# pmu.net
KiCad netlist of a schematic drawn in Altium Designer
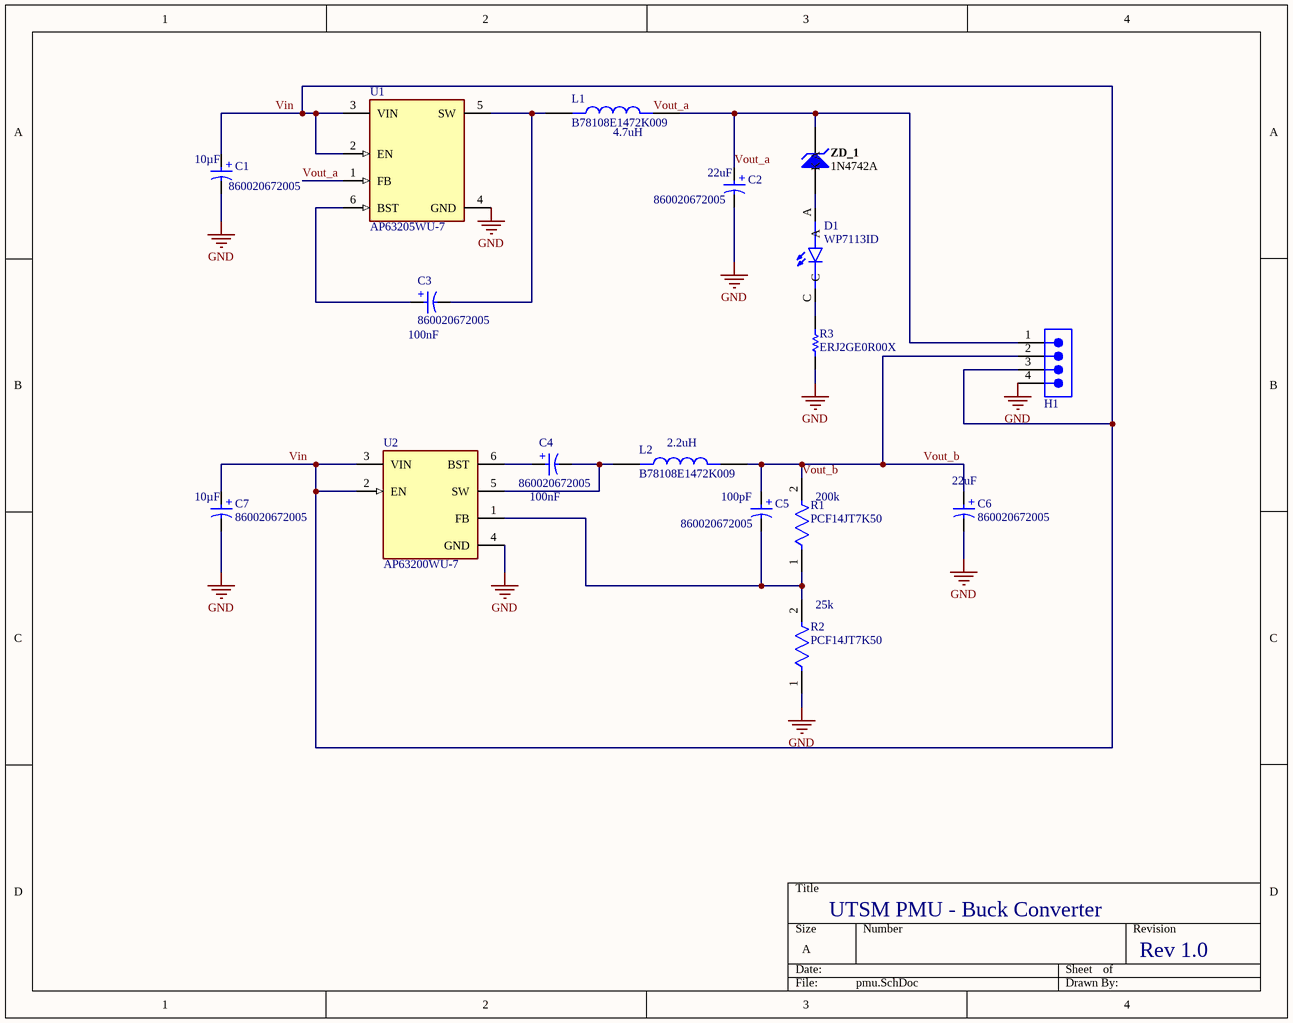
[diagram p0: pmu.SchDoc]

(export (version "E")
  (design (tool "Eeschema 10.0.6"))
  (components
    (comp (ref "C1")
      (value "860020672005")
      (footprint "WCAP-ATG5_D5H11")
      (description "860020672005 WCAP-ATG5 Aluminum Electrolytic Capacitors")
      (fields (field (name "TOLERANCE") "20%") (field (name "CAPACITANCE") "10µF"))
      (libsource (lib "Altium Content Vault") (part "Capacitor_Polarized"))
    )
    (comp (ref "C2")
      (value "860020672005")
      (footprint "WCAP-ATG5_D5H11")
      (description "860020672005 WCAP-ATG5 Aluminum Electrolytic Capacitors")
      (fields (field (name "TOLERANCE") "20%") (field (name "CAPACITANCE") "22uF"))
      (libsource (lib "Altium Content Vault") (part "Capacitor_Polarized"))
    )
    (comp (ref "C3")
      (value "860020672005")
      (footprint "WCAP-ATG5_D5H11")
      (description "860020672005 WCAP-ATG5 Aluminum Electrolytic Capacitors")
      (fields (field (name "TOLERANCE") "20%") (field (name "CAPACITANCE") "100nF"))
      (libsource (lib "Altium Content Vault") (part "Capacitor_Polarized"))
    )
    (comp (ref "C4")
      (value "860020672005")
      (footprint "WCAP-ATG5_D5H11")
      (description "860020672005 WCAP-ATG5 Aluminum Electrolytic Capacitors")
      (fields (field (name "TOLERANCE") "20%") (field (name "CAPACITANCE") "100nF"))
      (libsource (lib "Altium Content Vault") (part "Capacitor_Polarized"))
    )
    (comp (ref "C5")
      (value "860020672005")
      (footprint "WCAP-ATG5_D5H11")
      (description "860020672005 WCAP-ATG5 Aluminum Electrolytic Capacitors")
      (fields (field (name "TOLERANCE") "20%") (field (name "CAPACITANCE") "100pF"))
      (libsource (lib "Altium Content Vault") (part "Capacitor_Polarized"))
    )
    (comp (ref "C6")
      (value "860020672005")
      (footprint "WCAP-ATG5_D5H11")
      (description "860020672005 WCAP-ATG5 Aluminum Electrolytic Capacitors")
      (fields (field (name "TOLERANCE") "20%") (field (name "CAPACITANCE") "22uF"))
      (libsource (lib "Altium Content Vault") (part "Capacitor_Polarized"))
    )
    (comp (ref "C7")
      (value "860020672005")
      (footprint "WCAP-ATG5_D5H11")
      (description "860020672005 WCAP-ATG5 Aluminum Electrolytic Capacitors")
      (fields (field (name "TOLERANCE") "20%") (field (name "CAPACITANCE") "10µF"))
      (libsource (lib "Altium Content Vault") (part "Capacitor_Polarized"))
    )
    (comp (ref "D1")
      (value "WP7113ID")
      (footprint "LED_WP7113ID")
      (description "Red 617nm LED Indication - Discrete 2V Radial")
      (fields (field (name "MF") "Kingbright"))
      (libsource (lib "leds-WP7113ID") (part "WP7113ID"))
    )
    (comp (ref "H1")
      (value "61300411121")
      (footprint "61300411121")
      (description "WR-PHD Pin Header, THT, Vertical, pitch 2.54mm, 1 Row, 4P")
      (fields (field (name "MANUFACTURER") "Wurth Elektronik"))
      (libsource (lib "pmu") (part "61300411121"))
    )
    (comp (ref "L1")
      (value "B78108E1472K009")
      (footprint "INDAD1430W80L950D400")
      (description "4.7 ÂµH Unshielded Drum Core, Wirewound Inductor 2.75 A 85mOhm Max Axial")
      (fields
        (field (name "ALTIUM_VALUE") "4.7uH")
        (field (name "DIGI-KEY_PART_NUMBER") "495-76025-1-ND")
        (field (name "MF") "EPCOS")
      )
      (libsource (lib "B78108E1472K009") (part "B78108E1472K009"))
    )
    (comp (ref "L2")
      (value "B78108E1472K009")
      (footprint "INDAD1430W80L950D400")
      (description "4.7 ÂµH Unshielded Drum Core, Wirewound Inductor 2.75 A 85mOhm Max Axial")
      (fields
        (field (name "ALTIUM_VALUE") "2.2uH")
        (field (name "DIGI-KEY_PART_NUMBER") "495-76025-1-ND")
        (field (name "MF") "EPCOS")
      )
      (libsource (lib "B78108E1472K009") (part "B78108E1472K009"))
    )
    (comp (ref "R1")
      (value "PCF14JT7K50")
      (footprint "FP-CF14-MFG")
      (description "RES 7.5K OHM 1/4W 5% AXIAL")
      (fields (field (name "RESISTANCE") "200k") (field (name "TOLERANCE") "5%"))
      (libsource (lib "Altium Content Vault") (part "1029c3af85768c4190bb7ad29bc67b5"))
    )
    (comp (ref "R2")
      (value "PCF14JT7K50")
      (footprint "FP-CF14-MFG")
      (description "RES 7.5K OHM 1/4W 5% AXIAL")
      (fields (field (name "RESISTANCE") "25k") (field (name "TOLERANCE") "5%"))
      (libsource (lib "Altium Content Vault") (part "1029c3af85768c4190bb7ad29bc67b5"))
    )
    (comp (ref "R3")
      (value "ERJ2GE0R00X")
      (footprint "RESC1005X40X25LL05T05")
      (description "Chip Resistor, 0 Ohm, 0.1 W, -55 to 155 degC, 0402 (1005 Metric), RoHS, Tape and Reel")
      (fields (field (name "MANUFACTURER") "Panasonic") (field (name "TOLERANCE") "5%"))
      (libsource (lib "Altium Content Vault") (part "RES-2"))
    )
    (comp (ref "U1")
      (value "AP63205WU-7")
      (footprint "FP-TSOT26-MFG")
      (description "IC REG BUCK 5V 2A TSOT26")
      (fields
        (field (name "MANUFACTURER") "Diodes Inc.")
        (field (name "OCTOPART") "https://octopart.com/ap63205wu-7-diodes+inc.-98099551")
      )
      (libsource (lib "Altium Content Vault") (part "029bc9fbfa4a99dbb8b3a24c2adb655"))
    )
    (comp (ref "U2")
      (value "AP63200WU-7")
      (footprint "FP-TSOT26-MFG")
      (description "IC REG BUCK ADJUSTABLE 2A TSOT26")
      (fields
        (field (name "OCTOPART") "https://octopart.com/ap63200wu-7-diodes+inc.-98099548")
        (field (name "MANUFACTURER") "Diodes Inc.")
      )
      (libsource (lib "Altium Content Vault") (part "2ae3aed49e7ee94ca813948749813a1"))
    )
    (comp (ref "ZD_1")
      (value "1N4742A")
      (footprint "FAIR-DO-41-2_V")
      (description "Zener Diode, 12V, 1W, 5%, -65 to 200 degC, 2-Pin DO-41, Body 2.72 x 5.2 mm, RoHS")
      (fields (field (name "TOLERANCE") "5%") (field (name "MANUFACTURER") "Fairchild Semiconductor"))
      (libsource (lib "Altium Content Vault") (part "FAIR-DZEN-A1K2-2"))
    )
  )
  (nets
    (net (code "1") (name "/Vin") (class "Default")
      (node (ref "C1") (pin "1") (pinfunction "P_1") (pintype "passive"))
      (node (ref "C7") (pin "1") (pinfunction "P_1") (pintype "passive"))
      (node (ref "H1") (pin "3") (pinfunction "3_3") (pintype "passive"))
      (node (ref "U1") (pin "2") (pinfunction "EN_2") (pintype "input"))
      (node (ref "U1") (pin "3") (pinfunction "VIN_3") (pintype "power_in"))
      (node (ref "U2") (pin "2") (pinfunction "EN_2") (pintype "input"))
      (node (ref "U2") (pin "3") (pinfunction "VIN_3") (pintype "power_in"))
    )
    (net (code "2") (name "/Vout_a") (class "Default")
      (node (ref "C2") (pin "1") (pinfunction "P_1") (pintype "passive"))
      (node (ref "H1") (pin "1") (pinfunction "1_1") (pintype "passive"))
      (node (ref "L1") (pin "2") (pinfunction "2_2") (pintype "passive"))
      (node (ref "U1") (pin "1") (pinfunction "FB_1") (pintype "input"))
      (node (ref "ZD_1") (pin "2") (pinfunction "K_2") (pintype "passive"))
    )
    (net (code "3") (name "/Vout_b") (class "Default")
      (node (ref "C5") (pin "1") (pinfunction "P_1") (pintype "passive"))
      (node (ref "C6") (pin "1") (pinfunction "P_1") (pintype "passive"))
      (node (ref "H1") (pin "2") (pinfunction "2_2") (pintype "passive"))
      (node (ref "L2") (pin "2") (pinfunction "2_2") (pintype "passive"))
      (node (ref "R1") (pin "2") (pinfunction "2_2") (pintype "passive"))
    )
    (net (code "4") (name "GND") (class "Default")
      (node (ref "C1") (pin "2") (pinfunction "N_2") (pintype "passive"))
      (node (ref "C2") (pin "2") (pinfunction "N_2") (pintype "passive"))
      (node (ref "C6") (pin "2") (pinfunction "N_2") (pintype "passive"))
      (node (ref "C7") (pin "2") (pinfunction "N_2") (pintype "passive"))
      (node (ref "H1") (pin "4") (pinfunction "4_4") (pintype "passive"))
      (node (ref "R2") (pin "1") (pinfunction "1_1") (pintype "passive"))
      (node (ref "R3") (pin "1") (pinfunction "1_1") (pintype "passive"))
      (node (ref "U1") (pin "4") (pinfunction "GND_4") (pintype "power_in"))
      (node (ref "U2") (pin "4") (pinfunction "GND_4") (pintype "power_in"))
    )
    (net (code "5") (name "Net-(C3-N)") (class "Default")
      (node (ref "C3") (pin "2") (pinfunction "N_2") (pintype "passive"))
      (node (ref "L1") (pin "1") (pinfunction "1_1") (pintype "passive"))
      (node (ref "U1") (pin "5") (pinfunction "SW_5") (pintype "power_in"))
    )
    (net (code "6") (name "Net-(C3-P)") (class "Default")
      (node (ref "C3") (pin "1") (pinfunction "P_1") (pintype "passive"))
      (node (ref "U1") (pin "6") (pinfunction "BST_6") (pintype "input"))
    )
    (net (code "7") (name "Net-(C4-N)") (class "Default")
      (node (ref "C4") (pin "2") (pinfunction "N_2") (pintype "passive"))
      (node (ref "L2") (pin "1") (pinfunction "1_1") (pintype "passive"))
      (node (ref "U2") (pin "5") (pinfunction "SW_5") (pintype "passive"))
    )
    (net (code "8") (name "Net-(C4-P)") (class "Default")
      (node (ref "C4") (pin "1") (pinfunction "P_1") (pintype "passive"))
      (node (ref "U2") (pin "6") (pinfunction "BST_6") (pintype "passive"))
    )
    (net (code "9") (name "Net-(C5-N)") (class "Default")
      (node (ref "C5") (pin "2") (pinfunction "N_2") (pintype "passive"))
      (node (ref "R1") (pin "1") (pinfunction "1_1") (pintype "passive"))
      (node (ref "R2") (pin "2") (pinfunction "2_2") (pintype "passive"))
      (node (ref "U2") (pin "1") (pinfunction "FB_1") (pintype "passive"))
    )
    (net (code "10") (name "Net-(D1-PadC)") (class "Default")
      (node (ref "D1") (pin "C") (pinfunction "C_C") (pintype "passive"))
      (node (ref "R3") (pin "2") (pinfunction "2_2") (pintype "passive"))
    )
    (net (code "11") (name "Net-(ZD_1-A)") (class "Default")
      (node (ref "D1") (pin "A") (pinfunction "A_A") (pintype "passive"))
      (node (ref "ZD_1") (pin "1") (pinfunction "A_1") (pintype "passive"))
    )
  )
)
